# Top.net
KiCad netlist of a schematic drawn in Altium Designer
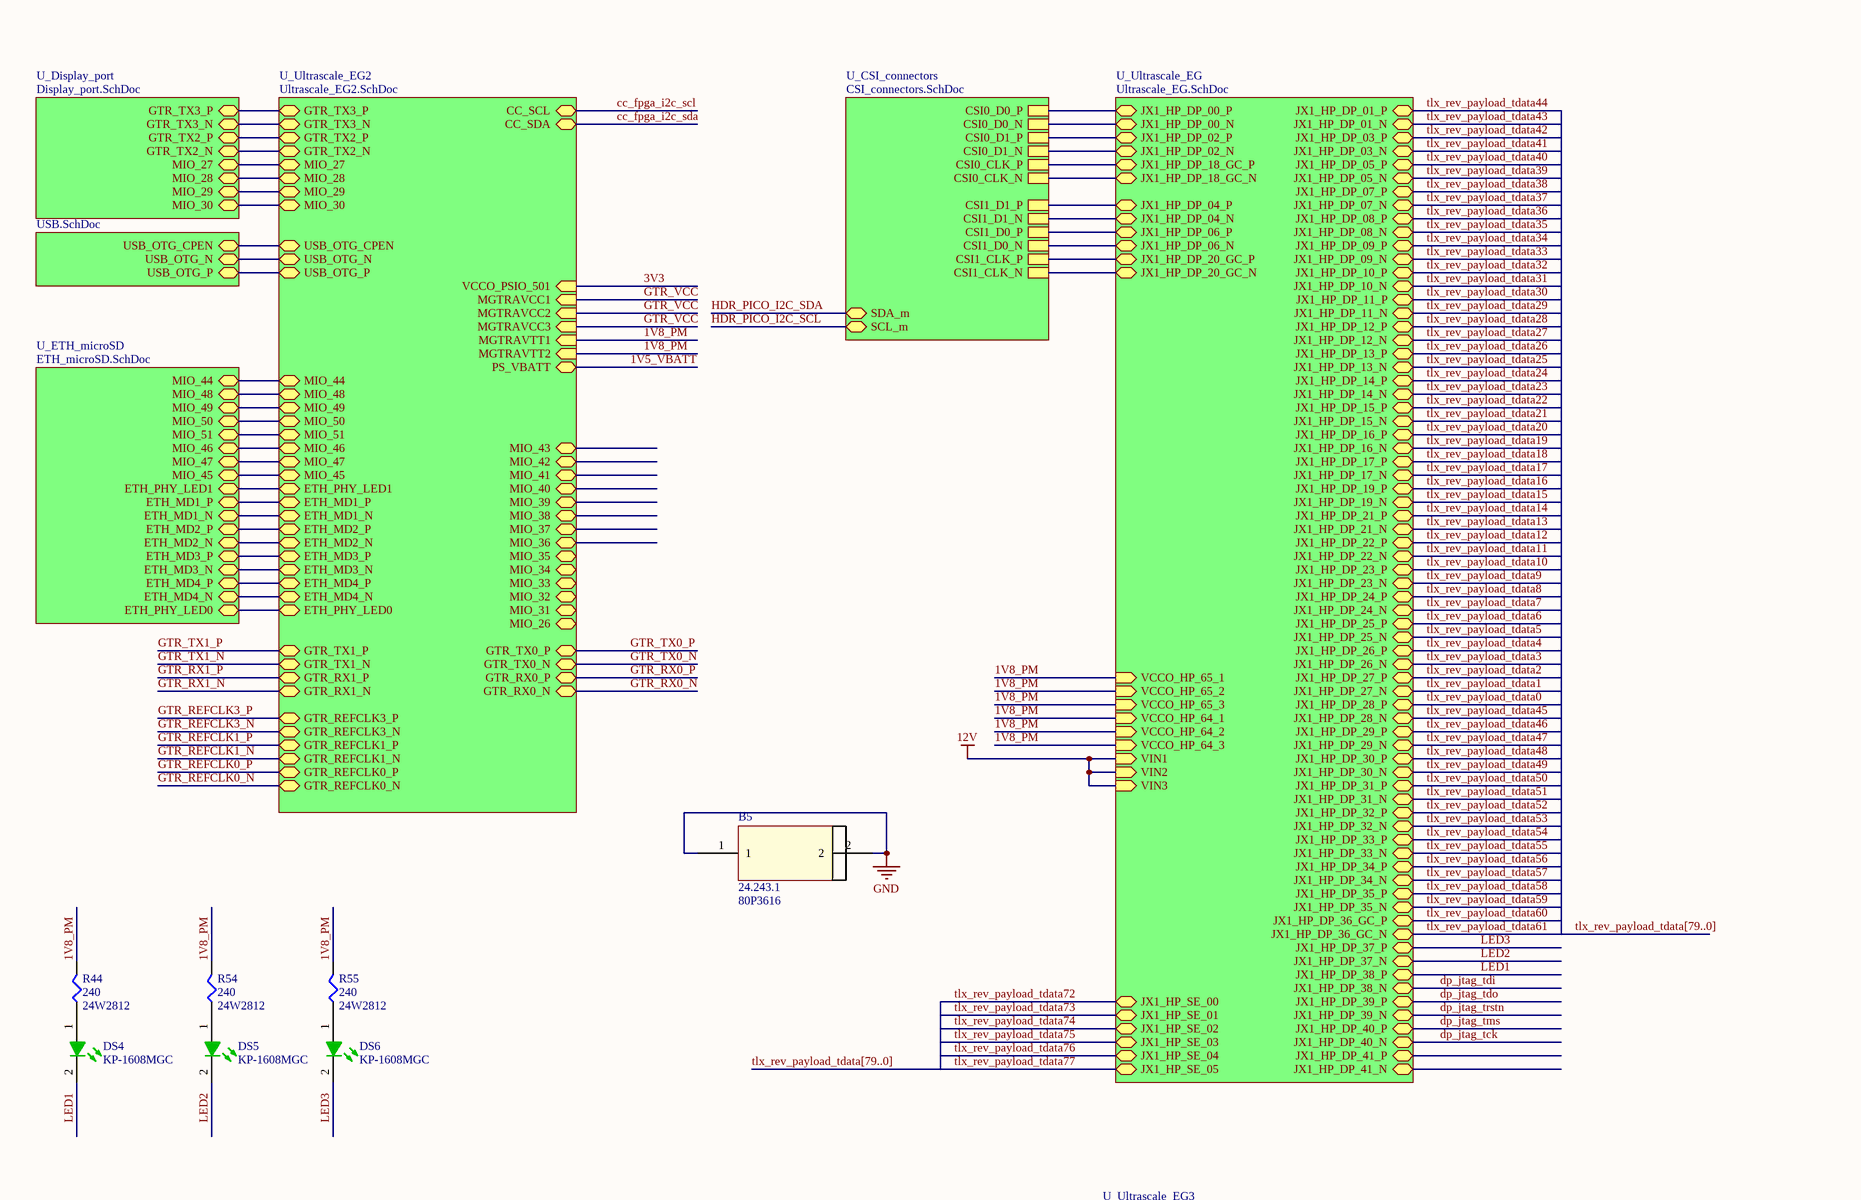
[diagram p0: Top.SchDoc, top left]
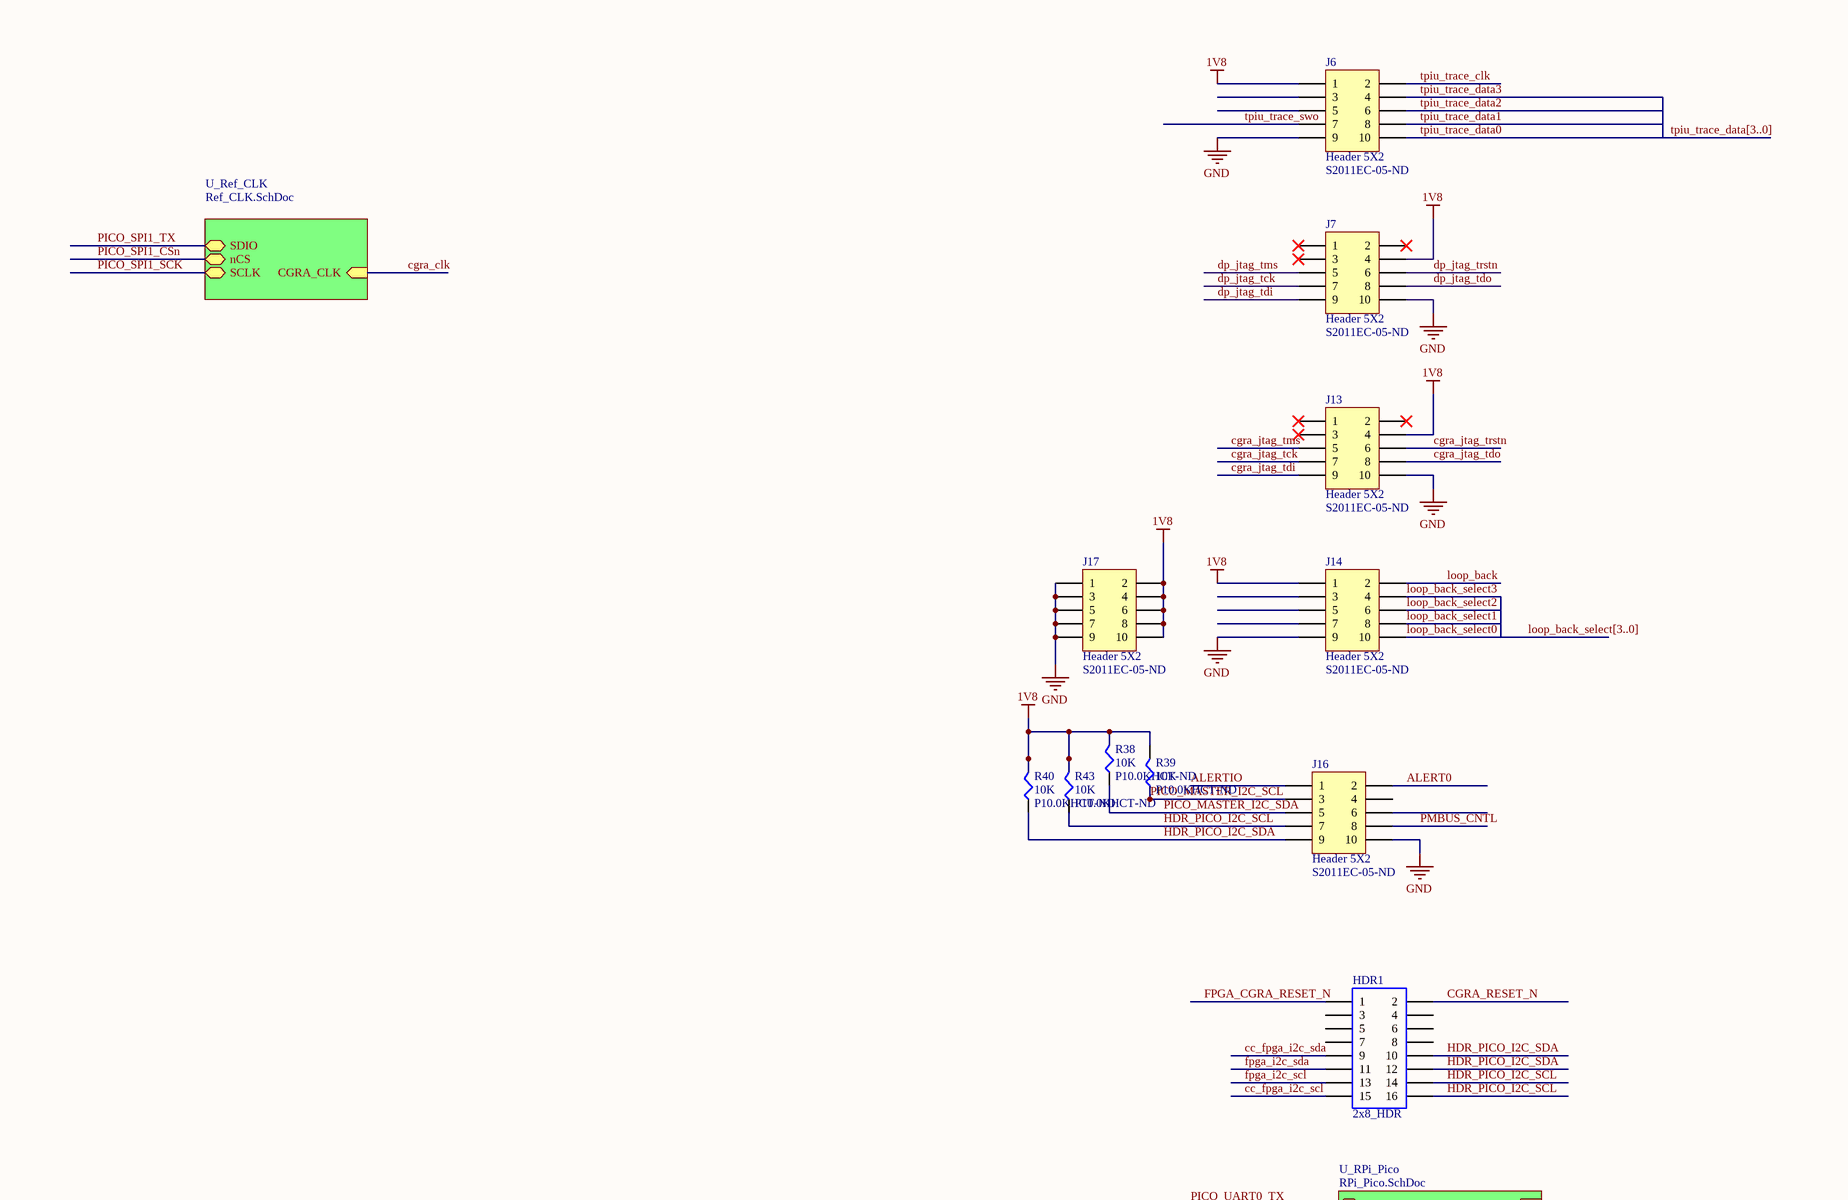
[diagram p1: Top.SchDoc, top right]
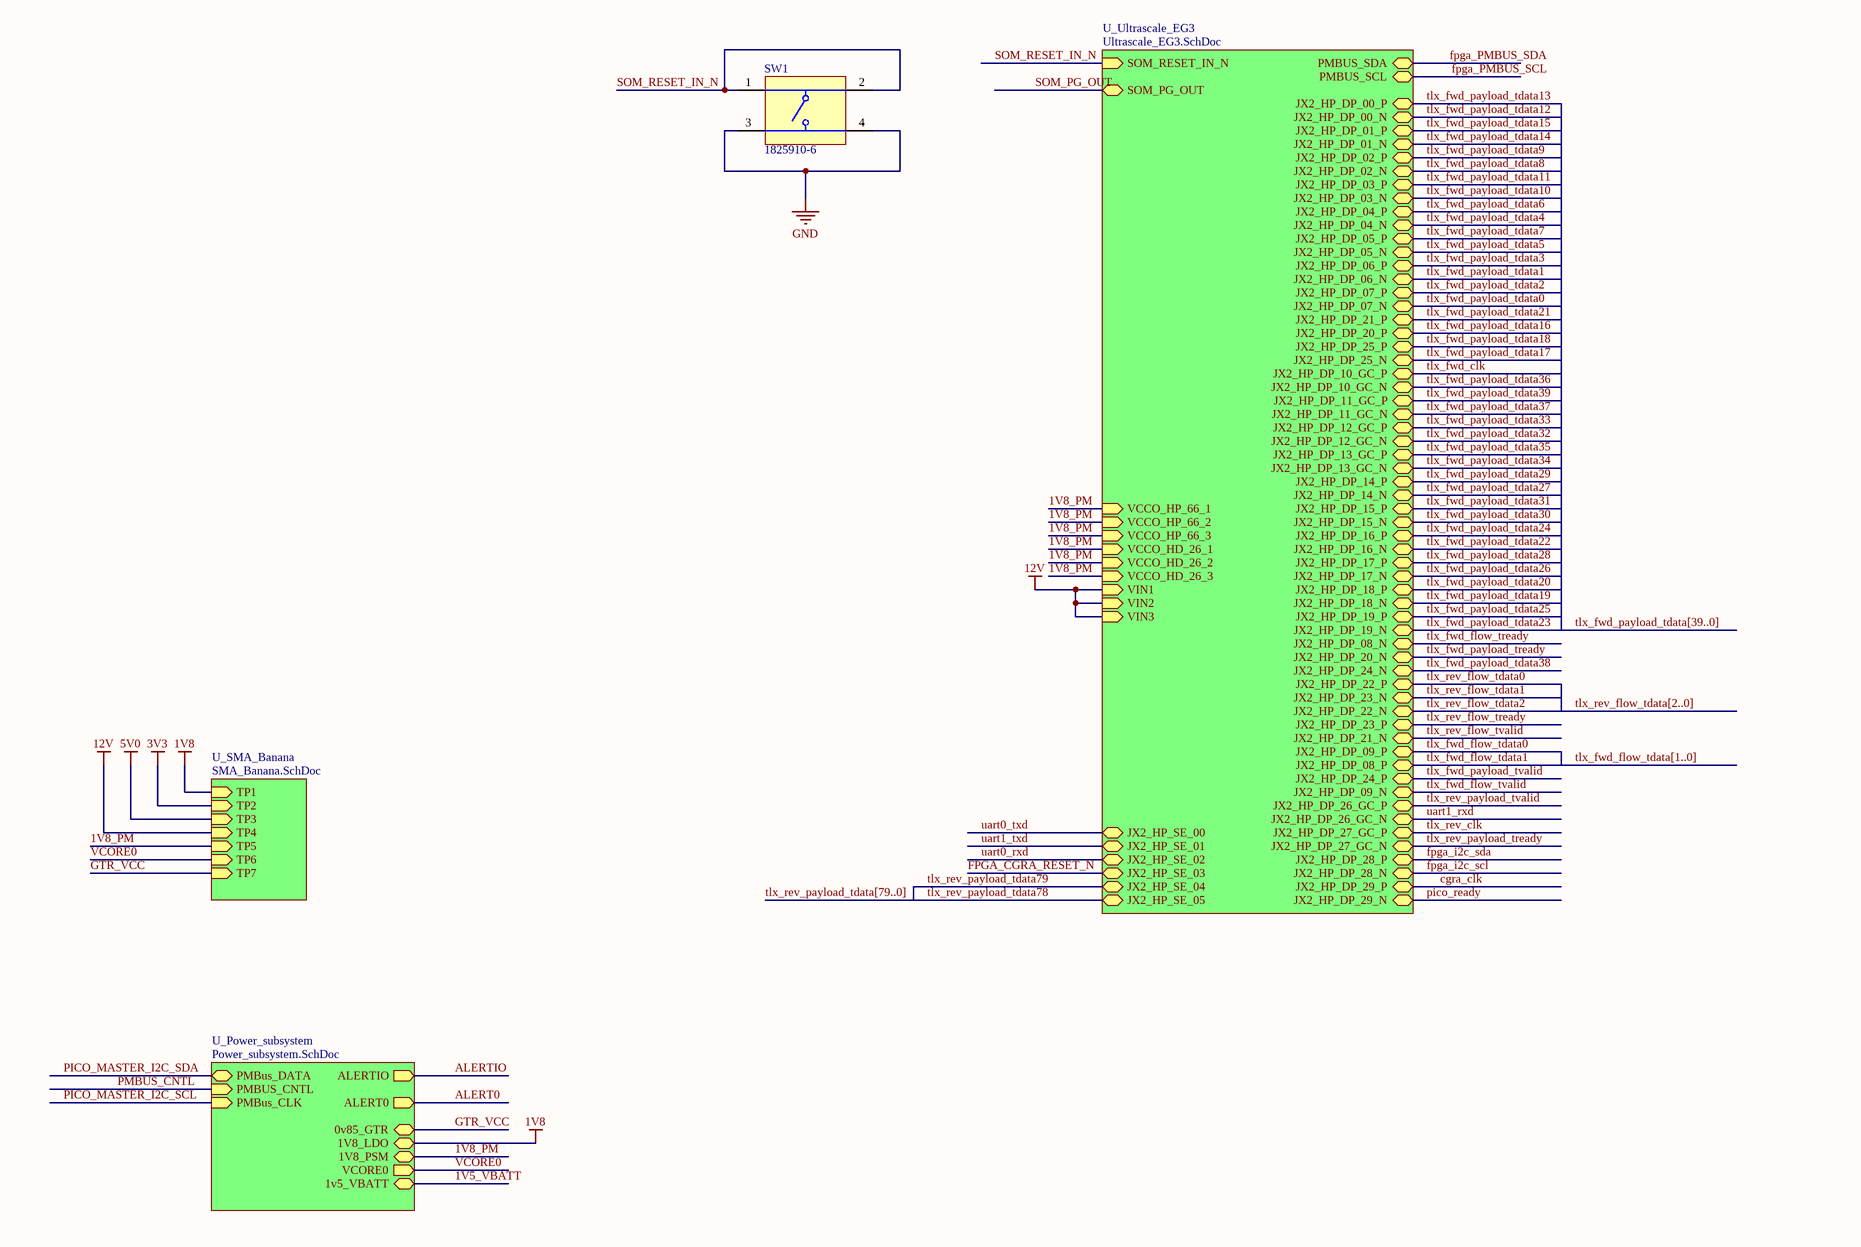
[diagram p2: Top.SchDoc, bottom left]
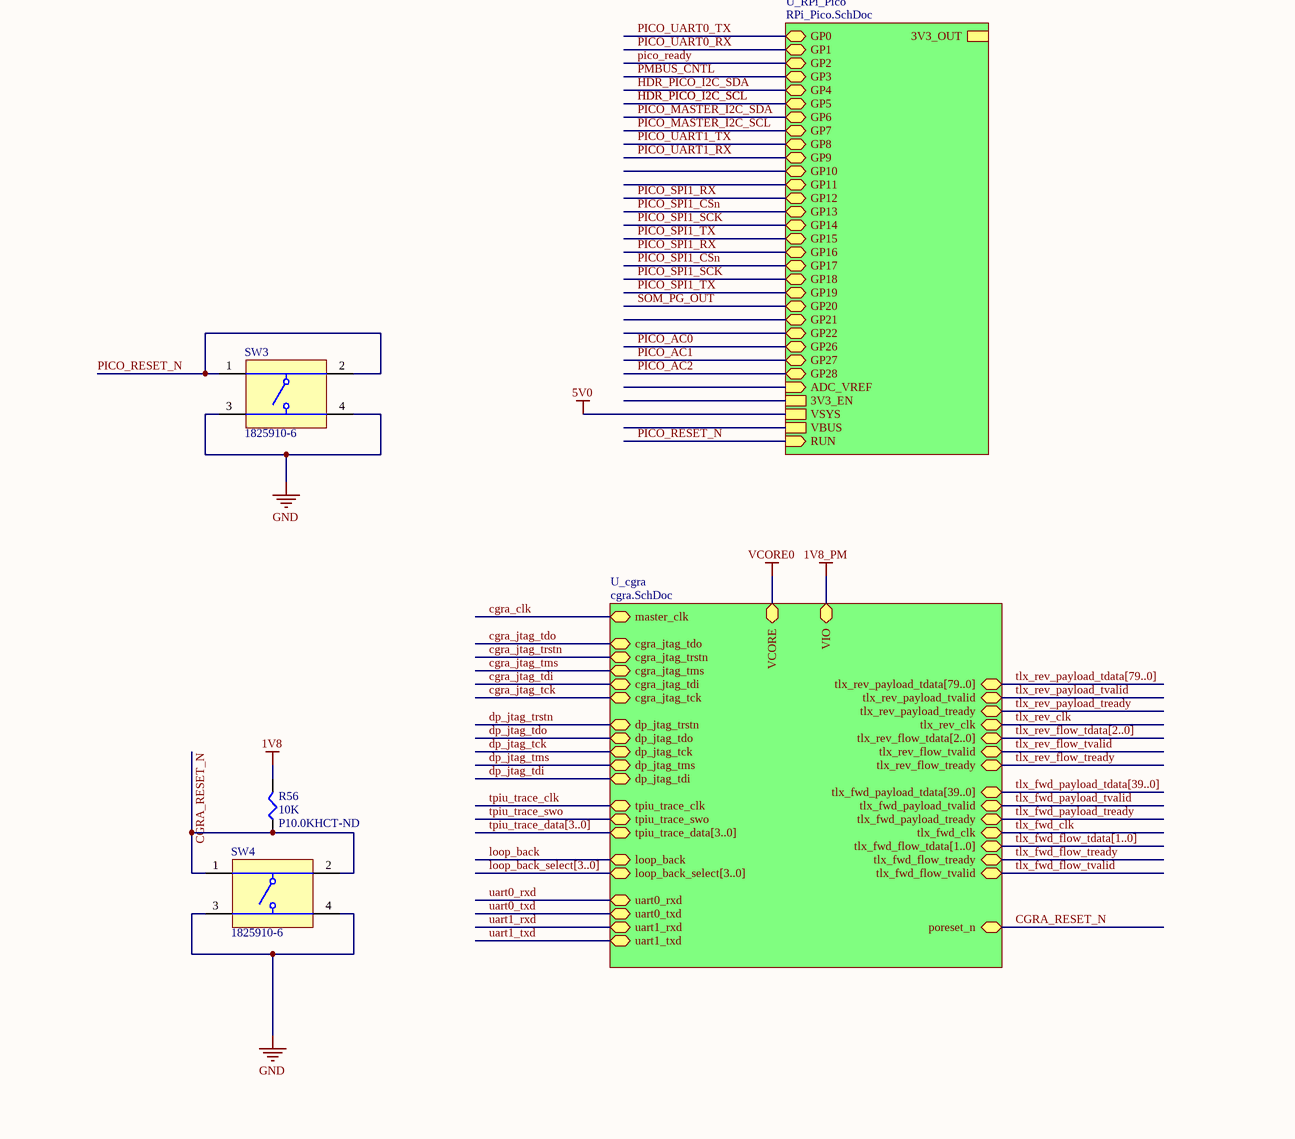
[diagram p3: Top.SchDoc, bottom right]

(export (version "E")
  (design (tool "Eeschema 10.0.6"))
  (components
    (comp (ref "B5")
      (value "24.243.1")
      (footprint "banana_clip")
      (fields (field (name "SUPPLIER PART NUMBER 1") "80P3616"))
      (libsource (lib "CGRA_schlib") (part "24.243.1"))
    )
    (comp (ref "DS4")
      (value "KP-1608MGC")
      (footprint "KING-0603LED_GREEN_V")
      (description "LED, SMT, 0603(1608), 1.1mm thickness, Green")
      (fields (field (name "MANUFACTURER") "Kingbright"))
      (libsource (lib "Altium Content Vault") (part "KING-LED-GREEN-A1K2-2"))
    )
    (comp (ref "DS5")
      (value "KP-1608MGC")
      (footprint "KING-0603LED_GREEN_V")
      (description "LED, SMT, 0603(1608), 1.1mm thickness, Green")
      (fields (field (name "MANUFACTURER") "Kingbright"))
      (libsource (lib "Altium Content Vault") (part "KING-LED-GREEN-A1K2-2"))
    )
    (comp (ref "DS6")
      (value "KP-1608MGC")
      (footprint "KING-0603LED_GREEN_V")
      (description "LED, SMT, 0603(1608), 1.1mm thickness, Green")
      (fields (field (name "MANUFACTURER") "Kingbright"))
      (libsource (lib "Altium Content Vault") (part "KING-LED-GREEN-A1K2-2"))
    )
    (comp (ref "HDR1")
      (value "2x8_HDR")
      (footprint "16POSHDR")
      (libsource (lib "CGRA_schlib") (part "2x8_HDR"))
    )
    (comp (ref "J6")
      (value "Header 5X2")
      (footprint "HDR2X5")
      (description "Header, 5-Pin, Dual row")
      (fields
        (field (name "SUPPLIER PART NUMBER 1") "S2011EC-05-ND")
        (field (name "PUBLISHER") "Altium Limited")
      )
      (libsource (lib "my_schsymbols") (part "Header 5X2"))
    )
    (comp (ref "J7")
      (value "Header 5X2")
      (footprint "HDR2X5")
      (description "Header, 5-Pin, Dual row")
      (fields
        (field (name "SUPPLIER PART NUMBER 1") "S2011EC-05-ND")
        (field (name "PUBLISHER") "Altium Limited")
      )
      (libsource (lib "my_schsymbols") (part "Header 5X2"))
    )
    (comp (ref "J13")
      (value "Header 5X2")
      (footprint "HDR2X5")
      (description "Header, 5-Pin, Dual row")
      (fields
        (field (name "SUPPLIER PART NUMBER 1") "S2011EC-05-ND")
        (field (name "PUBLISHER") "Altium Limited")
      )
      (libsource (lib "my_schsymbols") (part "Header 5X2"))
    )
    (comp (ref "J14")
      (value "Header 5X2")
      (footprint "HDR2X5")
      (description "Header, 5-Pin, Dual row")
      (fields
        (field (name "SUPPLIER PART NUMBER 1") "S2011EC-05-ND")
        (field (name "PUBLISHER") "Altium Limited")
      )
      (libsource (lib "my_schsymbols") (part "Header 5X2"))
    )
    (comp (ref "J16")
      (value "Header 5X2")
      (footprint "HDR2X5")
      (description "Header, 5-Pin, Dual row")
      (fields
        (field (name "SUPPLIER PART NUMBER 1") "S2011EC-05-ND")
        (field (name "PUBLISHER") "Altium Limited")
      )
      (libsource (lib "my_schsymbols") (part "Header 5X2"))
    )
    (comp (ref "J17")
      (value "Header 5X2")
      (footprint "HDR2X5")
      (description "Header, 5-Pin, Dual row")
      (fields
        (field (name "SUPPLIER PART NUMBER 1") "S2011EC-05-ND")
        (field (name "PUBLISHER") "Altium Limited")
      )
      (libsource (lib "my_schsymbols") (part "Header 5X2"))
    )
    (comp (ref "R38")
      (value "RES_10K_0603")
      (footprint "RESC1608X06N")
      (description "RES SMD 10K OHM 1% 1/4W 0603")
      (fields
        (field (name "MANUFACTURER") "Rohm")
        (field (name "MANUFACTURER PART NUMBER") "ESR03EZPF1002")
        (field (name "RESISTANCE") "10K")
        (field (name "SUPPLIER PART NUMBER 1") "P10.0KHCT-ND")
      )
      (libsource (lib "CGRA_schlib") (part "RES_10K_0603"))
    )
    (comp (ref "R39")
      (value "RES_10K_0603")
      (footprint "RESC1608X06N")
      (description "RES SMD 10K OHM 1% 1/4W 0603")
      (fields
        (field (name "MANUFACTURER") "Rohm")
        (field (name "MANUFACTURER PART NUMBER") "ESR03EZPF1002")
        (field (name "RESISTANCE") "10K")
        (field (name "SUPPLIER PART NUMBER 1") "P10.0KHCT-ND")
      )
      (libsource (lib "CGRA_schlib") (part "RES_10K_0603"))
    )
    (comp (ref "R40")
      (value "RES_10K_0603")
      (footprint "RESC1608X06N")
      (description "RES SMD 10K OHM 1% 1/4W 0603")
      (fields
        (field (name "MANUFACTURER") "Rohm")
        (field (name "MANUFACTURER PART NUMBER") "ESR03EZPF1002")
        (field (name "RESISTANCE") "10K")
        (field (name "SUPPLIER PART NUMBER 1") "P10.0KHCT-ND")
      )
      (libsource (lib "CGRA_schlib") (part "RES_10K_0603"))
    )
    (comp (ref "R43")
      (value "RES_10K_0603")
      (footprint "RESC1608X06N")
      (description "RES SMD 10K OHM 1% 1/4W 0603")
      (fields
        (field (name "MANUFACTURER") "Rohm")
        (field (name "MANUFACTURER PART NUMBER") "ESR03EZPF1002")
        (field (name "RESISTANCE") "10K")
        (field (name "SUPPLIER PART NUMBER 1") "P10.0KHCT-ND")
      )
      (libsource (lib "CGRA_schlib") (part "RES_10K_0603"))
    )
    (comp (ref "R44")
      (value "RES_240_0603")
      (footprint "RESC1608X06N")
      (description "Res Thin Film 0603 240 Ohm 0.1% 0.1W(1/10W) ±25ppm/C Molded SMD Automotive Punched T/R")
      (fields
        (field (name "MANUFACTURER") "Panasonic")
        (field (name "MANUFACTURER PART NUMBER") "ERA-3AEB101V")
        (field (name "RESISTANCE") "240")
        (field (name "SUPPLIER PART NUMBER 1") "24W2812")
      )
      (libsource (lib "CGRA_schlib") (part "RES_240_0603"))
    )
    (comp (ref "R54")
      (value "RES_240_0603")
      (footprint "RESC1608X06N")
      (description "Res Thin Film 0603 240 Ohm 0.1% 0.1W(1/10W) ±25ppm/C Molded SMD Automotive Punched T/R")
      (fields
        (field (name "MANUFACTURER") "Panasonic")
        (field (name "MANUFACTURER PART NUMBER") "ERA-3AEB101V")
        (field (name "RESISTANCE") "240")
        (field (name "SUPPLIER PART NUMBER 1") "24W2812")
      )
      (libsource (lib "CGRA_schlib") (part "RES_240_0603"))
    )
    (comp (ref "R55")
      (value "RES_240_0603")
      (footprint "RESC1608X06N")
      (description "Res Thin Film 0603 240 Ohm 0.1% 0.1W(1/10W) ±25ppm/C Molded SMD Automotive Punched T/R")
      (fields
        (field (name "MANUFACTURER") "Panasonic")
        (field (name "MANUFACTURER PART NUMBER") "ERA-3AEB101V")
        (field (name "RESISTANCE") "240")
        (field (name "SUPPLIER PART NUMBER 1") "24W2812")
      )
      (libsource (lib "CGRA_schlib") (part "RES_240_0603"))
    )
    (comp (ref "R56")
      (value "RES_10K_0603")
      (footprint "RESC1608X06N")
      (description "RES SMD 10K OHM 1% 1/4W 0603")
      (fields
        (field (name "MANUFACTURER") "Rohm")
        (field (name "MANUFACTURER PART NUMBER") "ESR03EZPF1002")
        (field (name "RESISTANCE") "10K")
        (field (name "SUPPLIER PART NUMBER 1") "P10.0KHCT-ND")
      )
      (libsource (lib "CGRA_schlib") (part "RES_10K_0603"))
    )
    (comp (ref "SW1")
      (value "1825910-6")
      (footprint "TECO-1825910-6_V")
      (description "Tact Switch, SPST-NO, 0.05 A, -35 to 85 degC, 4-Pin THD, RoHS, Bulk")
      (fields (field (name "MANUFACTURER") "TE Connectivity"))
      (libsource (lib "Altium Content Vault") (part "SW-SPST-4_A"))
    )
    (comp (ref "SW3")
      (value "1825910-6")
      (footprint "TECO-1825910-6_V")
      (description "Tact Switch, SPST-NO, 0.05 A, -35 to 85 degC, 4-Pin THD, RoHS, Bulk")
      (fields (field (name "MANUFACTURER") "TE Connectivity"))
      (libsource (lib "Altium Content Vault") (part "SW-SPST-4_A"))
    )
    (comp (ref "SW4")
      (value "1825910-6")
      (footprint "TECO-1825910-6_V")
      (description "Tact Switch, SPST-NO, 0.05 A, -35 to 85 degC, 4-Pin THD, RoHS, Bulk")
      (fields (field (name "MANUFACTURER") "TE Connectivity"))
      (libsource (lib "Altium Content Vault") (part "SW-SPST-4_A"))
    )
  )
  (nets
    (net (code "15") (name "/ALERT0") (class "Default")
      (node (ref "J16") (pin "2") (pinfunction "2_2") (pintype "passive"))
    )
    (net (code "16") (name "/ALERTIO") (class "Default")
      (node (ref "J16") (pin "1") (pinfunction "1_1") (pintype "passive"))
    )
    (net (code "17") (name "/CGRA_RESET_N") (class "Default")
      (node (ref "HDR1") (pin "2") (pinfunction "2_2") (pintype "passive"))
      (node (ref "R56") (pin "2") (pinfunction "2_2") (pintype "passive"))
      (node (ref "SW4") (pin "1") (pinfunction "1_1") (pintype "passive"))
      (node (ref "SW4") (pin "2") (pinfunction "2_2") (pintype "passive"))
    )
    (net (code "40") (name "/FPGA_CGRA_RESET_N") (class "Default")
      (node (ref "HDR1") (pin "1") (pinfunction "1_1") (pintype "passive"))
    )
    (net (code "64") (name "/HDR_PICO_I2C_SCL") (class "Default")
      (node (ref "HDR1") (pin "14") (pinfunction "14_14") (pintype "passive"))
      (node (ref "HDR1") (pin "16") (pinfunction "16_16") (pintype "passive"))
      (node (ref "J16") (pin "7") (pinfunction "7_7") (pintype "passive"))
      (node (ref "R43") (pin "2") (pinfunction "2_2") (pintype "passive"))
    )
    (net (code "65") (name "/HDR_PICO_I2C_SDA") (class "Default")
      (node (ref "HDR1") (pin "10") (pinfunction "10_10") (pintype "passive"))
      (node (ref "HDR1") (pin "12") (pinfunction "12_12") (pintype "passive"))
      (node (ref "J16") (pin "9") (pinfunction "9_9") (pintype "passive"))
      (node (ref "R40") (pin "2") (pinfunction "2_2") (pintype "passive"))
    )
    (net (code "68") (name "/LED1") (class "Default")
      (node (ref "DS4") (pin "2") (pinfunction "K_2") (pintype "passive"))
    )
    (net (code "69") (name "/LED2") (class "Default")
      (node (ref "DS5") (pin "2") (pinfunction "K_2") (pintype "passive"))
    )
    (net (code "70") (name "/LED3") (class "Default")
      (node (ref "DS6") (pin "2") (pinfunction "K_2") (pintype "passive"))
    )
    (net (code "100") (name "/PICO_MASTER_I2C_SCL") (class "Default")
      (node (ref "J16") (pin "3") (pinfunction "3_3") (pintype "passive"))
      (node (ref "R39") (pin "2") (pinfunction "2_2") (pintype "passive"))
    )
    (net (code "101") (name "/PICO_MASTER_I2C_SDA") (class "Default")
      (node (ref "J16") (pin "5") (pinfunction "5_5") (pintype "passive"))
      (node (ref "R38") (pin "2") (pinfunction "2_2") (pintype "passive"))
    )
    (net (code "102") (name "/PICO_RESET_N") (class "Default")
      (node (ref "SW3") (pin "1") (pinfunction "1_1") (pintype "passive"))
      (node (ref "SW3") (pin "2") (pinfunction "2_2") (pintype "passive"))
    )
    (net (code "111") (name "/PMBUS_CNTL") (class "Default")
      (node (ref "J16") (pin "8") (pinfunction "8_8") (pintype "passive"))
    )
    (net (code "113") (name "/SOM_RESET_IN_N") (class "Default")
      (node (ref "SW1") (pin "1") (pinfunction "1_1") (pintype "passive"))
      (node (ref "SW1") (pin "2") (pinfunction "2_2") (pintype "passive"))
    )
    (net (code "118") (name "/cc_fpga_i2c_scl") (class "Default")
      (node (ref "HDR1") (pin "15") (pinfunction "15_15") (pintype "passive"))
    )
    (net (code "119") (name "/cc_fpga_i2c_sda") (class "Default")
      (node (ref "HDR1") (pin "9") (pinfunction "9_9") (pintype "passive"))
    )
    (net (code "121") (name "/cgra_jtag_tck") (class "Default")
      (node (ref "J13") (pin "7") (pinfunction "7_7") (pintype "passive"))
    )
    (net (code "122") (name "/cgra_jtag_tdi") (class "Default")
      (node (ref "J13") (pin "9") (pinfunction "9_9") (pintype "passive"))
    )
    (net (code "123") (name "/cgra_jtag_tdo") (class "Default")
      (node (ref "J13") (pin "8") (pinfunction "8_8") (pintype "passive"))
    )
    (net (code "124") (name "/cgra_jtag_tms") (class "Default")
      (node (ref "J13") (pin "5") (pinfunction "5_5") (pintype "passive"))
    )
    (net (code "125") (name "/cgra_jtag_trstn") (class "Default")
      (node (ref "J13") (pin "6") (pinfunction "6_6") (pintype "passive"))
    )
    (net (code "126") (name "/dp_jtag_tck") (class "Default")
      (node (ref "J7") (pin "7") (pinfunction "7_7") (pintype "passive"))
    )
    (net (code "127") (name "/dp_jtag_tdi") (class "Default")
      (node (ref "J7") (pin "9") (pinfunction "9_9") (pintype "passive"))
    )
    (net (code "128") (name "/dp_jtag_tdo") (class "Default")
      (node (ref "J7") (pin "8") (pinfunction "8_8") (pintype "passive"))
    )
    (net (code "129") (name "/dp_jtag_tms") (class "Default")
      (node (ref "J7") (pin "5") (pinfunction "5_5") (pintype "passive"))
    )
    (net (code "130") (name "/dp_jtag_trstn") (class "Default")
      (node (ref "J7") (pin "6") (pinfunction "6_6") (pintype "passive"))
    )
    (net (code "133") (name "/fpga_i2c_scl") (class "Default")
      (node (ref "HDR1") (pin "13") (pinfunction "13_13") (pintype "passive"))
    )
    (net (code "134") (name "/fpga_i2c_sda") (class "Default")
      (node (ref "HDR1") (pin "11") (pinfunction "11_11") (pintype "passive"))
    )
    (net (code "135") (name "/loop_back") (class "Default")
      (node (ref "J14") (pin "2") (pinfunction "2_2") (pintype "passive"))
    )
    (net (code "136") (name "/loop_back_select0") (class "Default")
      (node (ref "J14") (pin "10") (pinfunction "10_10") (pintype "passive"))
    )
    (net (code "137") (name "/loop_back_select1") (class "Default")
      (node (ref "J14") (pin "8") (pinfunction "8_8") (pintype "passive"))
    )
    (net (code "138") (name "/loop_back_select2") (class "Default")
      (node (ref "J14") (pin "6") (pinfunction "6_6") (pintype "passive"))
    )
    (net (code "139") (name "/loop_back_select3") (class "Default")
      (node (ref "J14") (pin "4") (pinfunction "4_4") (pintype "passive"))
    )
    (net (code "271") (name "/tpiu_trace_clk") (class "Default")
      (node (ref "J6") (pin "2") (pinfunction "2_2") (pintype "passive"))
    )
    (net (code "272") (name "/tpiu_trace_data0") (class "Default")
      (node (ref "J6") (pin "10") (pinfunction "10_10") (pintype "passive"))
    )
    (net (code "273") (name "/tpiu_trace_data1") (class "Default")
      (node (ref "J6") (pin "8") (pinfunction "8_8") (pintype "passive"))
    )
    (net (code "274") (name "/tpiu_trace_data2") (class "Default")
      (node (ref "J6") (pin "6") (pinfunction "6_6") (pintype "passive"))
    )
    (net (code "275") (name "/tpiu_trace_data3") (class "Default")
      (node (ref "J6") (pin "4") (pinfunction "4_4") (pintype "passive"))
    )
    (net (code "277") (name "/tpiu_trace_swo") (class "Default")
      (node (ref "J6") (pin "7") (pinfunction "7_7") (pintype "passive"))
    )
    (net (code "282") (name "1V8") (class "Default")
      (node (ref "J13") (pin "4") (pinfunction "4_4") (pintype "passive"))
      (node (ref "J14") (pin "1") (pinfunction "1_1") (pintype "passive"))
      (node (ref "J17") (pin "10") (pinfunction "10_10") (pintype "passive"))
      (node (ref "J17") (pin "2") (pinfunction "2_2") (pintype "passive"))
      (node (ref "J17") (pin "4") (pinfunction "4_4") (pintype "passive"))
      (node (ref "J17") (pin "6") (pinfunction "6_6") (pintype "passive"))
      (node (ref "J17") (pin "8") (pinfunction "8_8") (pintype "passive"))
      (node (ref "J6") (pin "1") (pinfunction "1_1") (pintype "passive"))
      (node (ref "J7") (pin "4") (pinfunction "4_4") (pintype "passive"))
      (node (ref "R38") (pin "1") (pintype "passive"))
      (node (ref "R39") (pin "1") (pintype "passive"))
      (node (ref "R40") (pin "1") (pintype "passive"))
      (node (ref "R43") (pin "1") (pintype "passive"))
      (node (ref "R56") (pin "1") (pintype "passive"))
    )
    (net (code "283") (name "1V8_PM") (class "Default")
      (node (ref "R44") (pin "1") (pintype "passive"))
      (node (ref "R54") (pin "1") (pintype "passive"))
      (node (ref "R55") (pin "1") (pintype "passive"))
    )
    (net (code "287") (name "GND") (class "Default")
      (node (ref "B5") (pin "1") (pinfunction "1_1") (pintype "passive"))
      (node (ref "B5") (pin "2") (pinfunction "2_2") (pintype "passive"))
      (node (ref "J13") (pin "10") (pinfunction "10_10") (pintype "passive"))
      (node (ref "J14") (pin "9") (pinfunction "9_9") (pintype "passive"))
      (node (ref "J16") (pin "10") (pinfunction "10_10") (pintype "passive"))
      (node (ref "J17") (pin "1") (pinfunction "1_1") (pintype "passive"))
      (node (ref "J17") (pin "3") (pinfunction "3_3") (pintype "passive"))
      (node (ref "J17") (pin "5") (pinfunction "5_5") (pintype "passive"))
      (node (ref "J17") (pin "7") (pinfunction "7_7") (pintype "passive"))
      (node (ref "J17") (pin "9") (pinfunction "9_9") (pintype "passive"))
      (node (ref "J6") (pin "9") (pinfunction "9_9") (pintype "passive"))
      (node (ref "J7") (pin "10") (pinfunction "10_10") (pintype "passive"))
      (node (ref "SW1") (pin "3") (pinfunction "3_3") (pintype "passive"))
      (node (ref "SW1") (pin "4") (pinfunction "4_4") (pintype "passive"))
      (node (ref "SW3") (pin "3") (pinfunction "3_3") (pintype "passive"))
      (node (ref "SW3") (pin "4") (pinfunction "4_4") (pintype "passive"))
      (node (ref "SW4") (pin "3") (pinfunction "3_3") (pintype "passive"))
      (node (ref "SW4") (pin "4") (pinfunction "4_4") (pintype "passive"))
    )
    (net (code "288") (name "Net-(DS4-A)") (class "Default")
      (node (ref "DS4") (pin "1") (pinfunction "A_1") (pintype "passive"))
      (node (ref "R44") (pin "2") (pinfunction "2_2") (pintype "passive"))
    )
    (net (code "289") (name "Net-(DS5-A)") (class "Default")
      (node (ref "DS5") (pin "1") (pinfunction "A_1") (pintype "passive"))
      (node (ref "R54") (pin "2") (pinfunction "2_2") (pintype "passive"))
    )
    (net (code "290") (name "Net-(DS6-A)") (class "Default")
      (node (ref "DS6") (pin "1") (pinfunction "A_1") (pintype "passive"))
      (node (ref "R55") (pin "2") (pinfunction "2_2") (pintype "passive"))
    )
    (net (code "292") (name "unconnected-(HDR1-Pad3)") (class "Default")
      (node (ref "HDR1") (pin "3") (pinfunction "3_3") (pintype "passive"))
    )
    (net (code "293") (name "unconnected-(HDR1-Pad4)") (class "Default")
      (node (ref "HDR1") (pin "4") (pinfunction "4_4") (pintype "passive"))
    )
    (net (code "294") (name "unconnected-(HDR1-Pad5)") (class "Default")
      (node (ref "HDR1") (pin "5") (pinfunction "5_5") (pintype "passive"))
    )
    (net (code "295") (name "unconnected-(HDR1-Pad6)") (class "Default")
      (node (ref "HDR1") (pin "6") (pinfunction "6_6") (pintype "passive"))
    )
    (net (code "296") (name "unconnected-(HDR1-Pad7)") (class "Default")
      (node (ref "HDR1") (pin "7") (pinfunction "7_7") (pintype "passive"))
    )
    (net (code "297") (name "unconnected-(HDR1-Pad8)") (class "Default")
      (node (ref "HDR1") (pin "8") (pinfunction "8_8") (pintype "passive"))
    )
    (net (code "298") (name "unconnected-(J6-Pad3)") (class "Default")
      (node (ref "J6") (pin "3") (pinfunction "3_3") (pintype "passive"))
    )
    (net (code "299") (name "unconnected-(J6-Pad5)") (class "Default")
      (node (ref "J6") (pin "5") (pinfunction "5_5") (pintype "passive"))
    )
    (net (code "300") (name "unconnected-(J7-Pad1)") (class "Default")
      (node (ref "J7") (pin "1") (pinfunction "1_1") (pintype "passive+no_connect"))
    )
    (net (code "301") (name "unconnected-(J7-Pad2)") (class "Default")
      (node (ref "J7") (pin "2") (pinfunction "2_2") (pintype "passive+no_connect"))
    )
    (net (code "302") (name "unconnected-(J7-Pad3)") (class "Default")
      (node (ref "J7") (pin "3") (pinfunction "3_3") (pintype "passive+no_connect"))
    )
    (net (code "303") (name "unconnected-(J13-Pad1)") (class "Default")
      (node (ref "J13") (pin "1") (pinfunction "1_1") (pintype "passive+no_connect"))
    )
    (net (code "304") (name "unconnected-(J13-Pad2)") (class "Default")
      (node (ref "J13") (pin "2") (pinfunction "2_2") (pintype "passive+no_connect"))
    )
    (net (code "305") (name "unconnected-(J13-Pad3)") (class "Default")
      (node (ref "J13") (pin "3") (pinfunction "3_3") (pintype "passive+no_connect"))
    )
    (net (code "306") (name "unconnected-(J14-Pad3)") (class "Default")
      (node (ref "J14") (pin "3") (pinfunction "3_3") (pintype "passive"))
    )
    (net (code "307") (name "unconnected-(J14-Pad5)") (class "Default")
      (node (ref "J14") (pin "5") (pinfunction "5_5") (pintype "passive"))
    )
    (net (code "308") (name "unconnected-(J14-Pad7)") (class "Default")
      (node (ref "J14") (pin "7") (pinfunction "7_7") (pintype "passive"))
    )
    (net (code "309") (name "unconnected-(J16-Pad4)") (class "Default")
      (node (ref "J16") (pin "4") (pinfunction "4_4") (pintype "passive"))
    )
    (net (code "310") (name "unconnected-(J16-Pad6)") (class "Default")
      (node (ref "J16") (pin "6") (pinfunction "6_6") (pintype "passive"))
    )
  )
)
